# LPC1769test.net
KiCad netlist of a schematic drawn in Altium Designer
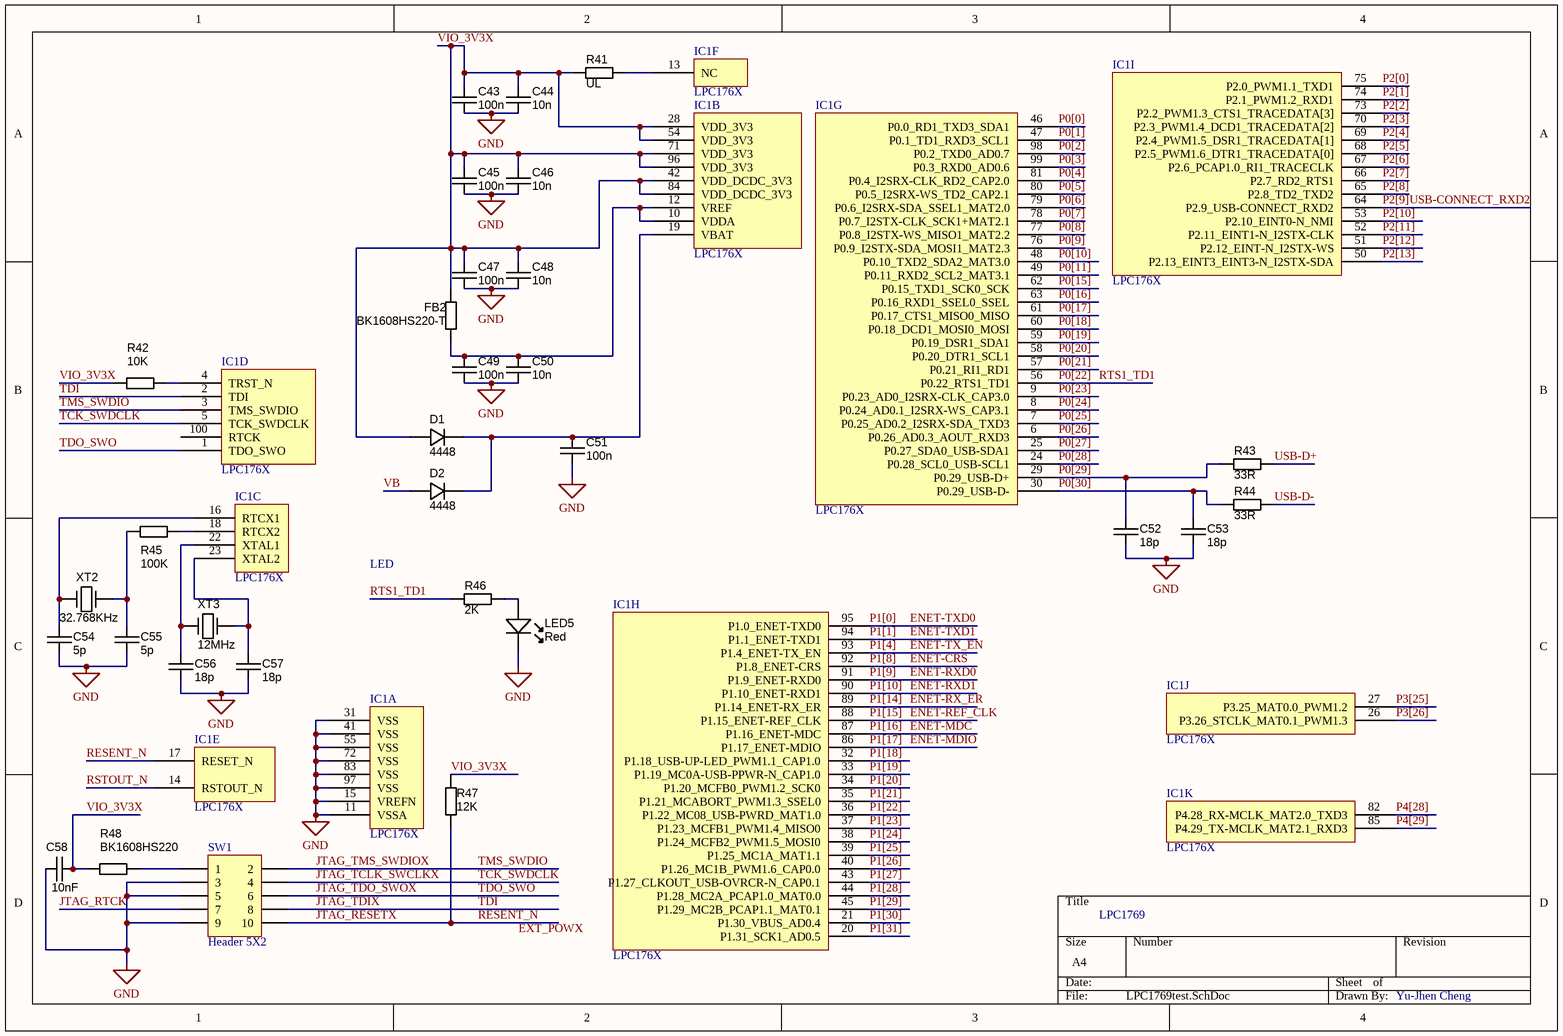
[diagram p0: LPC1769test.SchDoc]

(export (version "E")
  (design (tool "Eeschema 10.0.6"))
  (components
    (comp (ref "C43")
      (value "100n")
      (footprint "CAPC2012N")
      (description "Capacitor SMD Cer 100nF 10% 50V X7R 0805")
      (fields (field (name "TOLERANCE") "?0%") (field (name "Comment") "approved sub OK"))
      (libsource (lib "PBL - Capacitors") (part "CAPC_100n_0805"))
    )
    (comp (ref "C44")
      (value "10n")
      (footprint "CAPC2012N")
      (description "Capacitor SMD Cer 100nF 10% 50V X7R 0805")
      (fields (field (name "TOLERANCE") "?0%") (field (name "Comment") "approved sub OK"))
      (libsource (lib "PBL - Capacitors") (part "CAPC_100n_0805"))
    )
    (comp (ref "C45")
      (value "100n")
      (footprint "CAPC2012N")
      (description "Capacitor SMD Cer 100nF 10% 50V X7R 0805")
      (fields (field (name "TOLERANCE") "?0%") (field (name "Comment") "approved sub OK"))
      (libsource (lib "PBL - Capacitors") (part "CAPC_100n_0805"))
    )
    (comp (ref "C46")
      (value "10n")
      (footprint "CAPC2012N")
      (description "Capacitor SMD Cer 100nF 10% 50V X7R 0805")
      (fields (field (name "TOLERANCE") "?0%") (field (name "Comment") "approved sub OK"))
      (libsource (lib "PBL - Capacitors") (part "CAPC_100n_0805"))
    )
    (comp (ref "C47")
      (value "100n")
      (footprint "CAPC2012N")
      (description "Capacitor SMD Cer 100nF 10% 50V X7R 0805")
      (fields (field (name "TOLERANCE") "?0%") (field (name "Comment") "approved sub OK"))
      (libsource (lib "PBL - Capacitors") (part "CAPC_100n_0805"))
    )
    (comp (ref "C48")
      (value "10n")
      (footprint "CAPC2012N")
      (description "Capacitor SMD Cer 100nF 10% 50V X7R 0805")
      (fields (field (name "TOLERANCE") "?0%") (field (name "Comment") "approved sub OK"))
      (libsource (lib "PBL - Capacitors") (part "CAPC_100n_0805"))
    )
    (comp (ref "C49")
      (value "100n")
      (footprint "CAPC2012N")
      (description "Capacitor SMD Cer 100nF 10% 50V X7R 0805")
      (fields (field (name "TOLERANCE") "?0%") (field (name "Comment") "approved sub OK"))
      (libsource (lib "PBL - Capacitors") (part "CAPC_100n_0805"))
    )
    (comp (ref "C50")
      (value "10n")
      (footprint "CAPC2012N")
      (description "Capacitor SMD Cer 100nF 10% 50V X7R 0805")
      (fields (field (name "TOLERANCE") "?0%") (field (name "Comment") "approved sub OK"))
      (libsource (lib "PBL - Capacitors") (part "CAPC_100n_0805"))
    )
    (comp (ref "C51")
      (value "100n")
      (footprint "CAPC2012N")
      (description "Capacitor SMD Cer 100nF 10% 50V X7R 0805")
      (fields (field (name "TOLERANCE") "?0%") (field (name "Comment") "approved sub OK"))
      (libsource (lib "PBL - Capacitors") (part "CAPC_100n_0805"))
    )
    (comp (ref "C52")
      (value "18p")
      (footprint "CAPC2012N")
      (description "Capacitor SMD Cer 100nF 10% 50V X7R 0805")
      (fields (field (name "TOLERANCE") "?0%") (field (name "Comment") "approved sub OK"))
      (libsource (lib "PBL - Capacitors") (part "CAPC_100n_0805"))
    )
    (comp (ref "C53")
      (value "18p")
      (footprint "CAPC2012N")
      (description "Capacitor SMD Cer 100nF 10% 50V X7R 0805")
      (fields (field (name "TOLERANCE") "?0%") (field (name "Comment") "approved sub OK"))
      (libsource (lib "PBL - Capacitors") (part "CAPC_100n_0805"))
    )
    (comp (ref "C54")
      (value "5p")
      (footprint "CAPC2012N")
      (description "Capacitor SMD Cer 100nF 10% 50V X7R 0805")
      (fields (field (name "TOLERANCE") "?0%") (field (name "Comment") "approved sub OK"))
      (libsource (lib "PBL - Capacitors") (part "CAPC_100n_0805"))
    )
    (comp (ref "C55")
      (value "5p")
      (footprint "CAPC2012N")
      (description "Capacitor SMD Cer 100nF 10% 50V X7R 0805")
      (fields (field (name "TOLERANCE") "?0%") (field (name "Comment") "approved sub OK"))
      (libsource (lib "PBL - Capacitors") (part "CAPC_100n_0805"))
    )
    (comp (ref "C56")
      (value "18p")
      (footprint "CAPC2012N")
      (description "Capacitor SMD Cer 100nF 10% 50V X7R 0805")
      (fields (field (name "TOLERANCE") "?0%") (field (name "Comment") "approved sub OK"))
      (libsource (lib "PBL - Capacitors") (part "CAPC_100n_0805"))
    )
    (comp (ref "C57")
      (value "18p")
      (footprint "CAPC2012N")
      (description "Capacitor SMD Cer 100nF 10% 50V X7R 0805")
      (fields (field (name "TOLERANCE") "?0%") (field (name "Comment") "approved sub OK"))
      (libsource (lib "PBL - Capacitors") (part "CAPC_100n_0805"))
    )
    (comp (ref "C58")
      (value "10nF")
      (footprint "CAPC2012N")
      (description "Capacitor SMD Cer 100nF 10% 50V X7R 0805")
      (fields (field (name "TOLERANCE") "?0%") (field (name "Comment") "approved sub OK"))
      (libsource (lib "PBL - Capacitors") (part "CAPC_100n_0805"))
    )
    (comp (ref "D1")
      (value "4448")
      (footprint "SOD523F")
      (description "Diode SMD small signal 0.2A SOD-523F")
      (libsource (lib "PBL - Diodes") (part "DIODE_1N4148_200mA_SOD523F"))
    )
    (comp (ref "D2")
      (value "4448")
      (footprint "SOD523F")
      (description "Diode SMD small signal 0.2A SOD-523F")
      (libsource (lib "PBL - Diodes") (part "DIODE_1N4148_200mA_SOD523F"))
    )
    (comp (ref "FB2")
      (value "BK1608HS220-T")
      (footprint "RESC2012N")
      (description "Resistor SMD chip 10k Ohm 0.125W 5% 0805")
      (fields (field (name "TOLERANCE") "?%") (field (name "Comment") "Thick Film"))
      (libsource (lib "") (part "RES_10K_0805_5%_2"))
    )
    (comp (ref "IC1")
      (value "LPC176X")
      (footprint "TQFP-PT100_N")
      (libsource (lib "Schlib1") (part "LPC176X"))
    )
    (comp (ref "LED5")
      (value "Red")
      (footprint "LED-0805-A")
      (description "LED, 0805 SMD, Red")
      (libsource (lib "PBL - Light Sources") (part "LED_SMD_Red_0805"))
    )
    (comp (ref "R41")
      (value "UL")
      (footprint "RESC2012N")
      (description "Resistor SMD chip 10k Ohm 0.125W 5% 0805")
      (fields (field (name "TOLERANCE") "?%") (field (name "Comment") "Thick Film"))
      (libsource (lib "PBL - Resistors") (part "RES_10K_0805_5%"))
    )
    (comp (ref "R42")
      (value "10K")
      (footprint "RESC1005N")
      (description "Resistor SMD chip 330 Ohm 0.063W 5% 0402")
      (fields (field (name "TOLERANCE") "?%") (field (name "Comment") "Thick Film"))
      (libsource (lib "PBL - Resistors") (part "RES_330R_0402_5%"))
    )
    (comp (ref "R43")
      (value "33R")
      (footprint "RESC2012N")
      (description "Resistor SMD chip 10k Ohm 0.125W 5% 0805")
      (fields (field (name "TOLERANCE") "?%") (field (name "Comment") "Thick Film"))
      (libsource (lib "PBL - Resistors") (part "RES_10K_0805_5%"))
    )
    (comp (ref "R44")
      (value "33R")
      (footprint "RESC2012N")
      (description "Resistor SMD chip 10k Ohm 0.125W 5% 0805")
      (fields (field (name "TOLERANCE") "?%") (field (name "Comment") "Thick Film"))
      (libsource (lib "PBL - Resistors") (part "RES_10K_0805_5%"))
    )
    (comp (ref "R45")
      (value "100K")
      (footprint "RESC2012N")
      (description "Resistor SMD chip 10k Ohm 0.125W 5% 0805")
      (fields (field (name "TOLERANCE") "?%") (field (name "Comment") "Thick Film"))
      (libsource (lib "PBL - Resistors") (part "RES_10K_0805_5%"))
    )
    (comp (ref "R46")
      (value "2K")
      (footprint "RESC2012N")
      (description "Resistor SMD chip 10k Ohm 0.125W 5% 0805")
      (fields (field (name "TOLERANCE") "?%") (field (name "Comment") "Thick Film"))
      (libsource (lib "") (part "RES_10K_0805_5%_1"))
    )
    (comp (ref "R47")
      (value "12K")
      (footprint "RESC1005N")
      (description "Resistor SMD chip 330 Ohm 0.063W 5% 0402")
      (fields (field (name "TOLERANCE") "?%") (field (name "Comment") "Thick Film"))
      (libsource (lib "") (part "RES_330R_0402_5%_1"))
    )
    (comp (ref "R48")
      (value "BK1608HS220")
      (footprint "RESC2012N")
      (description "Resistor SMD chip 10k Ohm 0.125W 5% 0805")
      (fields (field (name "TOLERANCE") "?%") (field (name "Comment") "Thick Film"))
      (libsource (lib "PBL - Resistors") (part "RES_10K_0805_5%"))
    )
    (comp (ref "SW1")
      (value "Header 5X2")
      (footprint "HDR2X5")
      (description "Header, 5-Pin, Dual row")
      (fields (field (name "PUBLISHER") "Altium Limited"))
      (libsource (lib "Miscellaneous Connectors") (part "Header 5X2"))
    )
    (comp (ref "XT2")
      (value "32.768KHz")
      (footprint "CRYSTAL_HC49-US-SM")
      (description "Resonator Ceramic 6.00 MHz 30ppm")
      (libsource (lib "PBL - Resonators") (part "Crystal_6MHz_HC49/US"))
    )
    (comp (ref "XT3")
      (value "12MHz")
      (footprint "CRYSTAL_HC49-US-SM")
      (description "Resonator Ceramic 6.00 MHz 30ppm")
      (libsource (lib "PBL - Resonators") (part "Crystal_6MHz_HC49/US"))
    )
  )
  (nets
    (net (code "1") (name "/ENET-CRS") (class "Default")
      (node (ref "IC1") (pin "92") (pinfunction "P1.8_ENET-CRS_92") (pintype "passive"))
    )
    (net (code "2") (name "/ENET-MDC") (class "Default")
      (node (ref "IC1") (pin "87") (pinfunction "P1.16_ENET-MDC_87") (pintype "passive"))
    )
    (net (code "3") (name "/ENET-MDIO") (class "Default")
      (node (ref "IC1") (pin "86") (pinfunction "P1.17_ENET-MDIO_86") (pintype "passive"))
    )
    (net (code "4") (name "/ENET-REF_CLK") (class "Default")
      (node (ref "IC1") (pin "88") (pinfunction "P1.15_ENET-REF_CLK_88") (pintype "passive"))
    )
    (net (code "5") (name "/ENET-RXD0") (class "Default")
      (node (ref "IC1") (pin "91") (pinfunction "P1.9_ENET-RXD0_91") (pintype "passive"))
    )
    (net (code "6") (name "/ENET-RXD1") (class "Default")
      (node (ref "IC1") (pin "90") (pinfunction "P1.10_ENET-RXD1_90") (pintype "passive"))
    )
    (net (code "7") (name "/ENET-RX_ER") (class "Default")
      (node (ref "IC1") (pin "89") (pinfunction "P1.14_ENET-RX_ER_89") (pintype "passive"))
    )
    (net (code "8") (name "/ENET-TXD0") (class "Default")
      (node (ref "IC1") (pin "95") (pinfunction "P1.0_ENET-TXD0_95") (pintype "passive"))
    )
    (net (code "9") (name "/ENET-TXD1") (class "Default")
      (node (ref "IC1") (pin "94") (pinfunction "P1.1_ENET-TXD1_94") (pintype "passive"))
    )
    (net (code "10") (name "/ENET-TX_EN") (class "Default")
      (node (ref "IC1") (pin "93") (pinfunction "P1.4_ENET-TX_EN_93") (pintype "passive"))
    )
    (net (code "12") (name "/JTAG_RESETX") (class "Default")
      (node (ref "IC1") (pin "17") (pinfunction "RESET_N_17") (pintype "passive"))
      (node (ref "R47") (pin "1") (pinfunction "1_1") (pintype "passive"))
      (node (ref "SW1") (pin "10") (pinfunction "10_10") (pintype "passive"))
    )
    (net (code "13") (name "/JTAG_RTCK") (class "Default")
      (node (ref "SW1") (pin "7") (pinfunction "7_7") (pintype "passive"))
    )
    (net (code "14") (name "/JTAG_TCLK_SWCLKX") (class "Default")
      (node (ref "IC1") (pin "5") (pinfunction "TCK_SWDCLK_5") (pintype "passive"))
      (node (ref "SW1") (pin "4") (pinfunction "4_4") (pintype "passive"))
    )
    (net (code "15") (name "/JTAG_TDIX") (class "Default")
      (node (ref "IC1") (pin "2") (pinfunction "TDI_2") (pintype "passive"))
      (node (ref "SW1") (pin "8") (pinfunction "8_8") (pintype "passive"))
    )
    (net (code "16") (name "/JTAG_TDO_SWOX") (class "Default")
      (node (ref "IC1") (pin "1") (pinfunction "TDO_SWO_1") (pintype "passive"))
      (node (ref "SW1") (pin "6") (pinfunction "6_6") (pintype "passive"))
    )
    (net (code "17") (name "/JTAG_TMS_SWDIOX") (class "Default")
      (node (ref "IC1") (pin "3") (pinfunction "TMS_SWDIO_3") (pintype "passive"))
      (node (ref "SW1") (pin "2") (pinfunction "2_2") (pintype "passive"))
    )
    (net (code "18") (name "/P0[0]") (class "Default")
      (node (ref "IC1") (pin "46") (pinfunction "P0.0_RD1_TXD3_SDA1_46") (pintype "passive"))
    )
    (net (code "19") (name "/P0[1]") (class "Default")
      (node (ref "IC1") (pin "47") (pinfunction "P0.1_TD1_RXD3_SCL1_47") (pintype "passive"))
    )
    (net (code "20") (name "/P0[2]") (class "Default")
      (node (ref "IC1") (pin "98") (pinfunction "P0.2_TXD0_AD0.7_98") (pintype "passive"))
    )
    (net (code "21") (name "/P0[3]") (class "Default")
      (node (ref "IC1") (pin "99") (pinfunction "P0.3_RXD0_AD0.6_99") (pintype "passive"))
    )
    (net (code "22") (name "/P0[4]") (class "Default")
      (node (ref "IC1") (pin "81") (pinfunction "P0.4_I2SRX-CLK_RD2_CAP2.0_81") (pintype "passive"))
    )
    (net (code "23") (name "/P0[5]") (class "Default")
      (node (ref "IC1") (pin "80") (pinfunction "P0.5_I2SRX-WS_TD2_CAP2.1_80") (pintype "passive"))
    )
    (net (code "24") (name "/P0[6]") (class "Default")
      (node (ref "IC1") (pin "79") (pinfunction "P0.6_I2SRX-SDA_SSEL1_MAT2.0_79") (pintype "passive"))
    )
    (net (code "25") (name "/P0[7]") (class "Default")
      (node (ref "IC1") (pin "78") (pinfunction "P0.7_I2STX-CLK_SCK1+MAT2.1_78") (pintype "passive"))
    )
    (net (code "26") (name "/P0[8]") (class "Default")
      (node (ref "IC1") (pin "77") (pinfunction "P0.8_I2STX-WS_MISO1_MAT2.2_77") (pintype "passive"))
    )
    (net (code "27") (name "/P0[9]") (class "Default")
      (node (ref "IC1") (pin "76") (pinfunction "P0.9_I2STX-SDA_MOSI1_MAT2.3_76") (pintype "passive"))
    )
    (net (code "28") (name "/P0[10]") (class "Default")
      (node (ref "IC1") (pin "48") (pinfunction "P0.10_TXD2_SDA2_MAT3.0_48") (pintype "passive"))
    )
    (net (code "29") (name "/P0[11]") (class "Default")
      (node (ref "IC1") (pin "49") (pinfunction "P0.11_RXD2_SCL2_MAT3.1_49") (pintype "passive"))
    )
    (net (code "30") (name "/P0[15]") (class "Default")
      (node (ref "IC1") (pin "62") (pinfunction "P0.15_TXD1_SCK0_SCK_62") (pintype "passive"))
    )
    (net (code "31") (name "/P0[16]") (class "Default")
      (node (ref "IC1") (pin "63") (pinfunction "P0.16_RXD1_SSEL0_SSEL_63") (pintype "passive"))
    )
    (net (code "32") (name "/P0[17]") (class "Default")
      (node (ref "IC1") (pin "61") (pinfunction "P0.17_CTS1_MISO0_MISO_61") (pintype "passive"))
    )
    (net (code "33") (name "/P0[18]") (class "Default")
      (node (ref "IC1") (pin "60") (pinfunction "P0.18_DCD1_MOSI0_MOSI_60") (pintype "passive"))
    )
    (net (code "34") (name "/P0[19]") (class "Default")
      (node (ref "IC1") (pin "59") (pinfunction "P0.19_DSR1_SDA1_59") (pintype "passive"))
    )
    (net (code "35") (name "/P0[20]") (class "Default")
      (node (ref "IC1") (pin "58") (pinfunction "P0.20_DTR1_SCL1_58") (pintype "passive"))
    )
    (net (code "36") (name "/P0[21]") (class "Default")
      (node (ref "IC1") (pin "57") (pinfunction "P0.21_RI1_RD1_57") (pintype "passive"))
    )
    (net (code "37") (name "/P0[22]") (class "Default")
      (node (ref "IC1") (pin "56") (pinfunction "P0.22_RTS1_TD1_56") (pintype "passive"))
      (node (ref "R46") (pin "1") (pinfunction "1_1") (pintype "passive"))
    )
    (net (code "38") (name "/P0[23]") (class "Default")
      (node (ref "IC1") (pin "9") (pinfunction "P0.23_AD0_I2SRX-CLK_CAP3.0_9") (pintype "passive"))
    )
    (net (code "39") (name "/P0[24]") (class "Default")
      (node (ref "IC1") (pin "8") (pinfunction "P0.24_AD0.1_I2SRX-WS_CAP3.1_8") (pintype "passive"))
    )
    (net (code "40") (name "/P0[25]") (class "Default")
      (node (ref "IC1") (pin "7") (pinfunction "P0.25_AD0.2_I2SRX-SDA_TXD3_7") (pintype "passive"))
    )
    (net (code "41") (name "/P0[26]") (class "Default")
      (node (ref "IC1") (pin "6") (pinfunction "P0.26_AD0.3_AOUT_RXD3_6") (pintype "passive"))
    )
    (net (code "42") (name "/P0[27]") (class "Default")
      (node (ref "IC1") (pin "25") (pinfunction "P0.27_SDA0_USB-SDA1_25") (pintype "passive"))
    )
    (net (code "43") (name "/P0[28]") (class "Default")
      (node (ref "IC1") (pin "24") (pinfunction "P0.28_SCL0_USB-SCL1_24") (pintype "passive"))
    )
    (net (code "44") (name "/P0[29]") (class "Default")
      (node (ref "C52") (pin "2") (pintype "passive"))
      (node (ref "IC1") (pin "29") (pinfunction "P0.29_USB-D+_29") (pintype "passive"))
      (node (ref "R43") (pin "2") (pinfunction "2_2") (pintype "passive"))
    )
    (net (code "45") (name "/P0[30]") (class "Default")
      (node (ref "C53") (pin "2") (pintype "passive"))
      (node (ref "IC1") (pin "30") (pinfunction "P0.29_USB-D-_30") (pintype "passive"))
      (node (ref "R44") (pin "2") (pinfunction "2_2") (pintype "passive"))
    )
    (net (code "46") (name "/P1[18]") (class "Default")
      (node (ref "IC1") (pin "32") (pinfunction "P1.18_USB-UP-LED_PWM1.1_CAP1.0_32") (pintype "passive"))
    )
    (net (code "47") (name "/P1[19]") (class "Default")
      (node (ref "IC1") (pin "33") (pinfunction "P1.19_MC0A-USB-PPWR-N_CAP1.0_33") (pintype "passive"))
    )
    (net (code "48") (name "/P1[20]") (class "Default")
      (node (ref "IC1") (pin "34") (pinfunction "P1.20_MCFB0_PWM1.2_SCK0_34") (pintype "passive"))
    )
    (net (code "49") (name "/P1[21]") (class "Default")
      (node (ref "IC1") (pin "35") (pinfunction "P1.21_MCABORT_PWM1.3_SSEL0_35") (pintype "passive"))
    )
    (net (code "50") (name "/P1[22]") (class "Default")
      (node (ref "IC1") (pin "36") (pinfunction "P1.22_MC08_USB-PWRD_MAT1.0_36") (pintype "passive"))
    )
    (net (code "51") (name "/P1[23]") (class "Default")
      (node (ref "IC1") (pin "37") (pinfunction "P1.23_MCFB1_PWM1.4_MISO0_37") (pintype "passive"))
    )
    (net (code "52") (name "/P1[24]") (class "Default")
      (node (ref "IC1") (pin "38") (pinfunction "P1.24_MCFB2_PWM1.5_MOSI0_38") (pintype "passive"))
    )
    (net (code "53") (name "/P1[25]") (class "Default")
      (node (ref "IC1") (pin "39") (pinfunction "P1.25_MC1A_MAT1.1_39") (pintype "passive"))
    )
    (net (code "54") (name "/P1[26]") (class "Default")
      (node (ref "IC1") (pin "40") (pinfunction "P1.26_MC1B_PWM1.6_CAP0.0_40") (pintype "passive"))
    )
    (net (code "55") (name "/P1[27]") (class "Default")
      (node (ref "IC1") (pin "43") (pinfunction "P1.27_CLKOUT_USB-OVRCR-N_CAP0.1_43") (pintype "passive"))
    )
    (net (code "56") (name "/P1[28]") (class "Default")
      (node (ref "IC1") (pin "44") (pinfunction "P1.28_MC2A_PCAP1.0_MAT0.0_44") (pintype "passive"))
    )
    (net (code "57") (name "/P1[29]") (class "Default")
      (node (ref "IC1") (pin "45") (pinfunction "P1.29_MC2B_PCAP1.1_MAT0.1_45") (pintype "passive"))
    )
    (net (code "58") (name "/P1[30]") (class "Default")
      (node (ref "IC1") (pin "21") (pinfunction "P1.30_VBUS_AD0.4_21") (pintype "passive"))
    )
    (net (code "59") (name "/P1[31]") (class "Default")
      (node (ref "IC1") (pin "20") (pinfunction "P1.31_SCK1_AD0.5_20") (pintype "passive"))
    )
    (net (code "60") (name "/P2[0]") (class "Default")
      (node (ref "IC1") (pin "75") (pinfunction "P2.0_PWM1.1_TXD1_75") (pintype "passive"))
    )
    (net (code "61") (name "/P2[1]") (class "Default")
      (node (ref "IC1") (pin "74") (pinfunction "P2.1_PWM1.2_RXD1_74") (pintype "passive"))
    )
    (net (code "62") (name "/P2[2]") (class "Default")
      (node (ref "IC1") (pin "73") (pinfunction "P2.2_PWM1.3_CTS1_TRACEDATA[3]_73") (pintype "passive"))
    )
    (net (code "63") (name "/P2[3]") (class "Default")
      (node (ref "IC1") (pin "70") (pinfunction "P2.3_PWM1.4_DCD1_TRACEDATA[2]_70") (pintype "passive"))
    )
    (net (code "64") (name "/P2[4]") (class "Default")
      (node (ref "IC1") (pin "69") (pinfunction "P2.4_PWM1.5_DSR1_TRACEDATA[1]_69") (pintype "passive"))
    )
    (net (code "65") (name "/P2[5]") (class "Default")
      (node (ref "IC1") (pin "68") (pinfunction "P2.5_PWM1.6_DTR1_TRACEDATA[0]_68") (pintype "passive"))
    )
    (net (code "66") (name "/P2[6]") (class "Default")
      (node (ref "IC1") (pin "67") (pinfunction "P2.6_PCAP1.0_RI1_TRACECLK_67") (pintype "passive"))
    )
    (net (code "67") (name "/P2[7]") (class "Default")
      (node (ref "IC1") (pin "66") (pinfunction "P2.7_RD2_RTS1_66") (pintype "passive"))
    )
    (net (code "68") (name "/P2[8]") (class "Default")
      (node (ref "IC1") (pin "65") (pinfunction "P2.8_TD2_TXD2_65") (pintype "passive"))
    )
    (net (code "69") (name "/P2[9]") (class "Default")
      (node (ref "IC1") (pin "64") (pinfunction "P2.9_USB-CONNECT_RXD2_64") (pintype "passive"))
    )
    (net (code "70") (name "/P2[10]") (class "Default")
      (node (ref "IC1") (pin "53") (pinfunction "P2.10_EINT0-N_NMI_53") (pintype "passive"))
    )
    (net (code "71") (name "/P2[11]") (class "Default")
      (node (ref "IC1") (pin "52") (pinfunction "P2.11_EINT1-N_I2STX-CLK_52") (pintype "passive"))
    )
    (net (code "72") (name "/P2[12]") (class "Default")
      (node (ref "IC1") (pin "51") (pinfunction "P2.12_EINT-N_I2STX-WS_51") (pintype "passive"))
    )
    (net (code "73") (name "/P2[13]") (class "Default")
      (node (ref "IC1") (pin "50") (pinfunction "P2.13_EINT3_EINT3-N_I2STX-SDA_50") (pintype "passive"))
    )
    (net (code "74") (name "/P3[25]") (class "Default")
      (node (ref "IC1") (pin "27") (pinfunction "P3.25_MAT0.0_PWM1.2_27") (pintype "passive"))
    )
    (net (code "75") (name "/P3[26]") (class "Default")
      (node (ref "IC1") (pin "26") (pinfunction "P3.26_STCLK_MAT0.1_PWM1.3_26") (pintype "passive"))
    )
    (net (code "76") (name "/P4[28]") (class "Default")
      (node (ref "IC1") (pin "82") (pinfunction "P4.28_RX-MCLK_MAT2.0_TXD3_82") (pintype "passive"))
    )
    (net (code "77") (name "/P4[29]") (class "Default")
      (node (ref "IC1") (pin "85") (pinfunction "P4.29_TX-MCLK_MAT2.1_RXD3_85") (pintype "passive"))
    )
    (net (code "78") (name "/RSTOUT_N") (class "Default")
      (node (ref "IC1") (pin "14") (pinfunction "RSTOUT_N_14") (pintype "passive"))
    )
    (net (code "79") (name "/USB-D+") (class "Default")
      (node (ref "R43") (pin "1") (pinfunction "1_1") (pintype "passive"))
    )
    (net (code "80") (name "/USB-D-") (class "Default")
      (node (ref "R44") (pin "1") (pinfunction "1_1") (pintype "passive"))
    )
    (net (code "81") (name "/VB") (class "Default")
      (node (ref "D2") (pin "A") (pinfunction "A_A") (pintype "passive"))
    )
    (net (code "82") (name "/VIO_3V3X") (class "Default")
      (node (ref "C43") (pin "2") (pintype "passive"))
      (node (ref "C44") (pin "2") (pintype "passive"))
      (node (ref "C45") (pin "2") (pintype "passive"))
      (node (ref "C46") (pin "2") (pintype "passive"))
      (node (ref "C47") (pin "2") (pintype "passive"))
      (node (ref "C48") (pin "2") (pintype "passive"))
      (node (ref "C58") (pin "2") (pintype "passive"))
      (node (ref "D1") (pin "A") (pinfunction "A_A") (pintype "passive"))
      (node (ref "FB2") (pin "2") (pinfunction "2_2") (pintype "passive"))
      (node (ref "IC1") (pin "28") (pinfunction "VDD_3V3_28") (pintype "passive"))
      (node (ref "IC1") (pin "42") (pinfunction "VDD_DCDC_3V3_42") (pintype "passive"))
      (node (ref "IC1") (pin "54") (pinfunction "VDD_3V3_54") (pintype "passive"))
      (node (ref "IC1") (pin "71") (pinfunction "VDD_3V3_71") (pintype "passive"))
      (node (ref "IC1") (pin "84") (pinfunction "VDD_DCDC_3V3_84") (pintype "passive"))
      (node (ref "IC1") (pin "96") (pinfunction "VDD_3V3_96") (pintype "passive"))
      (node (ref "R41") (pin "2") (pinfunction "2_2") (pintype "passive"))
      (node (ref "R42") (pin "1") (pinfunction "1_1") (pintype "passive"))
      (node (ref "R47") (pin "2") (pinfunction "2_2") (pintype "passive"))
      (node (ref "R48") (pin "2") (pinfunction "2_2") (pintype "passive"))
    )
    (net (code "83") (name "GND") (class "Default")
      (node (ref "C43") (pin "1") (pintype "passive"))
      (node (ref "C44") (pin "1") (pintype "passive"))
      (node (ref "C45") (pin "1") (pintype "passive"))
      (node (ref "C46") (pin "1") (pintype "passive"))
      (node (ref "C47") (pin "1") (pintype "passive"))
      (node (ref "C48") (pin "1") (pintype "passive"))
      (node (ref "C49") (pin "1") (pintype "passive"))
      (node (ref "C50") (pin "1") (pintype "passive"))
      (node (ref "C51") (pin "1") (pintype "passive"))
      (node (ref "C52") (pin "1") (pintype "passive"))
      (node (ref "C53") (pin "1") (pintype "passive"))
      (node (ref "C54") (pin "1") (pintype "passive"))
      (node (ref "C55") (pin "1") (pintype "passive"))
      (node (ref "C56") (pin "1") (pintype "passive"))
      (node (ref "C57") (pin "1") (pintype "passive"))
      (node (ref "C58") (pin "1") (pintype "passive"))
      (node (ref "IC1") (pin "11") (pinfunction "VSSA_11") (pintype "passive"))
      (node (ref "IC1") (pin "15") (pinfunction "VREFN_15") (pintype "passive"))
      (node (ref "IC1") (pin "31") (pinfunction "VSS_31") (pintype "passive"))
      (node (ref "IC1") (pin "41") (pinfunction "VSS_41") (pintype "passive"))
      (node (ref "IC1") (pin "55") (pinfunction "VSS_55") (pintype "passive"))
      (node (ref "IC1") (pin "72") (pinfunction "VSS_72") (pintype "passive"))
      (node (ref "IC1") (pin "83") (pinfunction "VSS_83") (pintype "passive"))
      (node (ref "IC1") (pin "97") (pinfunction "VSS_97") (pintype "passive"))
      (node (ref "LED5") (pin "K") (pinfunction "K_K") (pintype "passive"))
      (node (ref "SW1") (pin "3") (pinfunction "3_3") (pintype "passive"))
      (node (ref "SW1") (pin "5") (pinfunction "5_5") (pintype "passive"))
      (node (ref "SW1") (pin "9") (pinfunction "9_9") (pintype "passive"))
    )
    (net (code "84") (name "Net-(IC1B-VBAT)") (class "Default")
      (node (ref "C51") (pin "2") (pintype "passive"))
      (node (ref "D1") (pin "K") (pinfunction "K_K") (pintype "passive"))
      (node (ref "D2") (pin "K") (pinfunction "K_K") (pintype "passive"))
      (node (ref "IC1") (pin "19") (pinfunction "VBAT_19") (pintype "passive"))
    )
    (net (code "85") (name "Net-(IC1B-VDDA)") (class "Default")
      (node (ref "C49") (pin "2") (pintype "passive"))
      (node (ref "C50") (pin "2") (pintype "passive"))
      (node (ref "FB2") (pin "1") (pinfunction "1_1") (pintype "passive"))
      (node (ref "IC1") (pin "10") (pinfunction "VDDA_10") (pintype "passive"))
      (node (ref "IC1") (pin "12") (pinfunction "VREF_12") (pintype "passive"))
    )
    (net (code "86") (name "Net-(IC1C-RTCX1)") (class "Default")
      (node (ref "C54") (pin "2") (pintype "passive"))
      (node (ref "IC1") (pin "16") (pinfunction "RTCX1_16") (pintype "passive"))
      (node (ref "XT2") (pin "1") (pinfunction "IN_1") (pintype "passive"))
    )
    (net (code "87") (name "Net-(IC1C-RTCX2)") (class "Default")
      (node (ref "IC1") (pin "18") (pinfunction "RTCX2_18") (pintype "passive"))
      (node (ref "R45") (pin "1") (pinfunction "1_1") (pintype "passive"))
    )
    (net (code "88") (name "Net-(IC1C-XTAL1)") (class "Default")
      (node (ref "C56") (pin "2") (pintype "passive"))
      (node (ref "IC1") (pin "22") (pinfunction "XTAL1_22") (pintype "passive"))
      (node (ref "XT3") (pin "1") (pinfunction "IN_1") (pintype "passive"))
    )
    (net (code "89") (name "Net-(IC1C-XTAL2)") (class "Default")
      (node (ref "C57") (pin "2") (pintype "passive"))
      (node (ref "IC1") (pin "23") (pinfunction "XTAL2_23") (pintype "passive"))
      (node (ref "XT3") (pin "2") (pinfunction "OUT_2") (pintype "passive"))
    )
    (net (code "90") (name "Net-(IC1D-TRST_N)") (class "Default")
      (node (ref "IC1") (pin "4") (pinfunction "TRST_N_4") (pintype "passive"))
      (node (ref "R42") (pin "2") (pinfunction "2_2") (pintype "passive"))
    )
    (net (code "91") (name "Net-(IC1F-NC)") (class "Default")
      (node (ref "IC1") (pin "13") (pinfunction "NC_13") (pintype "passive"))
      (node (ref "R41") (pin "1") (pinfunction "1_1") (pintype "passive"))
    )
    (net (code "92") (name "Net-(LED5-PadA)") (class "Default")
      (node (ref "LED5") (pin "A") (pinfunction "A_A") (pintype "passive"))
      (node (ref "R46") (pin "2") (pinfunction "2_2") (pintype "passive"))
    )
    (net (code "93") (name "Net-(R48-Pad1)") (class "Default")
      (node (ref "R48") (pin "1") (pinfunction "1_1") (pintype "passive"))
      (node (ref "SW1") (pin "1") (pinfunction "1_1") (pintype "passive"))
    )
    (net (code "94") (name "Net-(XT2-OUT)") (class "Default")
      (node (ref "C55") (pin "2") (pintype "passive"))
      (node (ref "R45") (pin "2") (pinfunction "2_2") (pintype "passive"))
      (node (ref "XT2") (pin "2") (pinfunction "OUT_2") (pintype "passive"))
    )
    (net (code "95") (name "unconnected-(IC1D-RTCK-Pad100)") (class "Default")
      (node (ref "IC1") (pin "100") (pinfunction "RTCK_100") (pintype "passive"))
    )
  )
)
